# DronePCB_2.net
KiCad netlist of a schematic drawn in Altium Designer
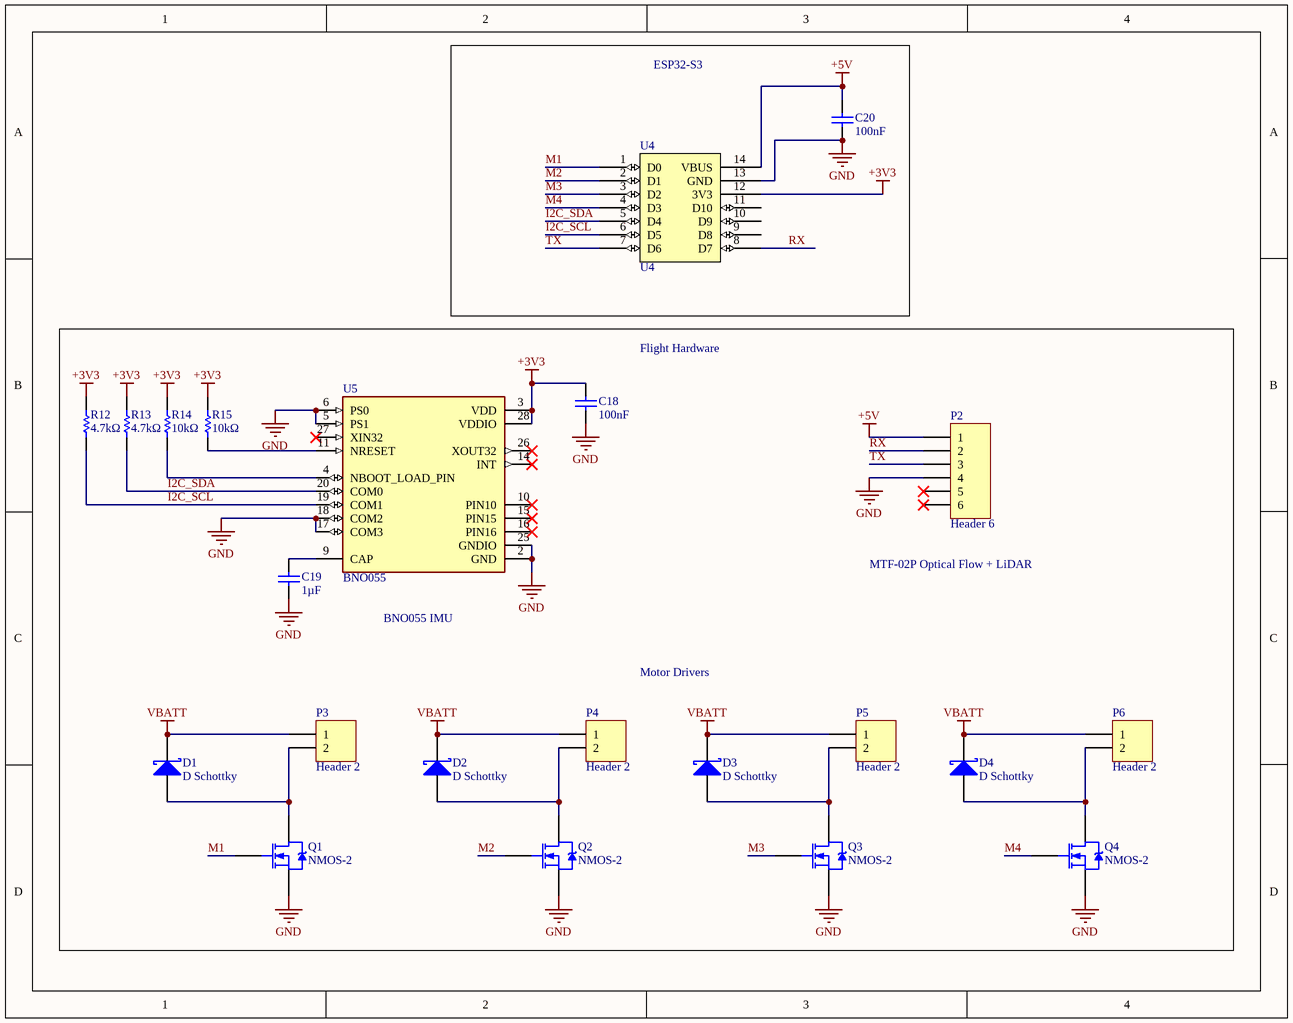
[diagram p0: DronePCB_2.SchDoc]

(export (version "E")
  (design (tool "Eeschema 10.0.6"))
  (components
    (comp (ref "C18")
      (value "100nF")
      (footprint "RAD-0.3")
      (description "Capacitor")
      (fields (field (name "Comment") "Cap") (field (name "PUBLISHER") "Altium Limited"))
      (libsource (lib "Miscellaneous Devices") (part "Cap"))
    )
    (comp (ref "C19")
      (value "1µF")
      (footprint "RAD-0.3")
      (description "Capacitor")
      (fields (field (name "Comment") "Cap") (field (name "PUBLISHER") "Altium Limited"))
      (libsource (lib "Miscellaneous Devices") (part "Cap"))
    )
    (comp (ref "C20")
      (value "100nF")
      (footprint "RAD-0.3")
      (description "Capacitor")
      (fields (field (name "Comment") "Cap") (field (name "PUBLISHER") "Altium Limited"))
      (libsource (lib "Miscellaneous Devices") (part "Cap"))
    )
    (comp (ref "D1")
      (value "D Schottky")
      (footprint "SMB")
      (description "Schottky Diode")
      (fields (field (name "PUBLISHER") "Altium Limited"))
      (libsource (lib "Miscellaneous Devices") (part "D Schottky"))
    )
    (comp (ref "D2")
      (value "D Schottky")
      (footprint "SMB")
      (description "Schottky Diode")
      (fields (field (name "PUBLISHER") "Altium Limited"))
      (libsource (lib "Miscellaneous Devices") (part "D Schottky"))
    )
    (comp (ref "D3")
      (value "D Schottky")
      (footprint "SMB")
      (description "Schottky Diode")
      (fields (field (name "PUBLISHER") "Altium Limited"))
      (libsource (lib "Miscellaneous Devices") (part "D Schottky"))
    )
    (comp (ref "D4")
      (value "D Schottky")
      (footprint "SMB")
      (description "Schottky Diode")
      (fields (field (name "PUBLISHER") "Altium Limited"))
      (libsource (lib "Miscellaneous Devices") (part "D Schottky"))
    )
    (comp (ref "P2")
      (value "Header 6")
      (footprint "HDR1X6")
      (description "Header, 6-Pin")
      (fields (field (name "PUBLISHER") "Altium Limited"))
      (libsource (lib "Miscellaneous Connectors") (part "Header 6"))
    )
    (comp (ref "P3")
      (value "Header 2")
      (footprint "HDR1X2")
      (description "Header, 2-Pin")
      (fields (field (name "PUBLISHER") "Altium Limited"))
      (libsource (lib "Miscellaneous Connectors") (part "Header 2"))
    )
    (comp (ref "P4")
      (value "Header 2")
      (footprint "HDR1X2")
      (description "Header, 2-Pin")
      (fields (field (name "PUBLISHER") "Altium Limited"))
      (libsource (lib "Miscellaneous Connectors") (part "Header 2"))
    )
    (comp (ref "P5")
      (value "Header 2")
      (footprint "HDR1X2")
      (description "Header, 2-Pin")
      (fields (field (name "PUBLISHER") "Altium Limited"))
      (libsource (lib "Miscellaneous Connectors") (part "Header 2"))
    )
    (comp (ref "P6")
      (value "Header 2")
      (footprint "HDR1X2")
      (description "Header, 2-Pin")
      (fields (field (name "PUBLISHER") "Altium Limited"))
      (libsource (lib "Miscellaneous Connectors") (part "Header 2"))
    )
    (comp (ref "Q1")
      (value "NMOS-2")
      (footprint "TO-220AB")
      (description "N-Channel Power MOSFET")
      (fields (field (name "PUBLISHER") "Altium Limited"))
      (libsource (lib "Miscellaneous Devices") (part "NMOS-2"))
    )
    (comp (ref "Q2")
      (value "NMOS-2")
      (footprint "TO-220AB")
      (description "N-Channel Power MOSFET")
      (fields (field (name "PUBLISHER") "Altium Limited"))
      (libsource (lib "Miscellaneous Devices") (part "NMOS-2"))
    )
    (comp (ref "Q3")
      (value "NMOS-2")
      (footprint "TO-220AB")
      (description "N-Channel Power MOSFET")
      (fields (field (name "PUBLISHER") "Altium Limited"))
      (libsource (lib "Miscellaneous Devices") (part "NMOS-2"))
    )
    (comp (ref "Q4")
      (value "NMOS-2")
      (footprint "TO-220AB")
      (description "N-Channel Power MOSFET")
      (fields (field (name "PUBLISHER") "Altium Limited"))
      (libsource (lib "Miscellaneous Devices") (part "NMOS-2"))
    )
    (comp (ref "R12")
      (value "4.7kΩ")
      (footprint "AXIAL-0.3")
      (description "Resistor")
      (fields (field (name "Comment") "Res1") (field (name "PUBLISHER") "Altium Limited"))
      (libsource (lib "Miscellaneous Devices") (part "Res1"))
    )
    (comp (ref "R13")
      (value "4.7kΩ")
      (footprint "AXIAL-0.3")
      (description "Resistor")
      (fields (field (name "Comment") "Res1") (field (name "PUBLISHER") "Altium Limited"))
      (libsource (lib "Miscellaneous Devices") (part "Res1"))
    )
    (comp (ref "R14")
      (value "10kΩ")
      (footprint "AXIAL-0.3")
      (description "Resistor")
      (fields (field (name "Comment") "Res1") (field (name "PUBLISHER") "Altium Limited"))
      (libsource (lib "Miscellaneous Devices") (part "Res1"))
    )
    (comp (ref "R15")
      (value "10kΩ")
      (footprint "AXIAL-0.3")
      (description "Resistor")
      (fields (field (name "Comment") "Res1") (field (name "PUBLISHER") "Altium Limited"))
      (libsource (lib "Miscellaneous Devices") (part "Res1"))
    )
    (comp (ref "U4") (value "U4") (libsource (lib "DronePCB_Main") (part "ESP32S3")))
    (comp (ref "U5")
      (value "BNO055")
      (footprint "LGA28R50P4X10_380X520X100:LGA28R50P4X10_380X520X100")
      (description "BNO055 9-axis Absolute Orientation Sensor ( SiP ) w/Sensors and Sensor Fusion")
      (libsource (lib "DronePCB_Main") (part "BNO055"))
    )
  )
  (nets
    (net (code "1") (name "+3V3") (class "Default")
      (node (ref "C18") (pin "2") (pinfunction "2_2") (pintype "passive"))
      (node (ref "R12") (pin "2") (pinfunction "2_2") (pintype "passive"))
      (node (ref "R13") (pin "2") (pinfunction "2_2") (pintype "passive"))
      (node (ref "R14") (pin "1") (pinfunction "1_1") (pintype "passive"))
      (node (ref "R15") (pin "1") (pinfunction "1_1") (pintype "passive"))
      (node (ref "U4") (pin "12") (pinfunction "3V3_12") (pintype "power_in"))
      (node (ref "U5") (pin "28") (pinfunction "VDDIO_28") (pintype "power_in"))
      (node (ref "U5") (pin "3") (pinfunction "VDD_3") (pintype "power_in"))
    )
    (net (code "2") (name "+5V") (class "Default")
      (node (ref "C20") (pin "2") (pinfunction "2_2") (pintype "passive"))
      (node (ref "P2") (pin "1") (pinfunction "1_1") (pintype "passive"))
      (node (ref "U4") (pin "14") (pinfunction "VBUS_14") (pintype "power_in"))
    )
    (net (code "3") (name "/I2C_SCL") (class "Default")
      (node (ref "R12") (pin "1") (pinfunction "1_1") (pintype "passive"))
      (node (ref "U4") (pin "6") (pinfunction "D5_6") (pintype "bidirectional"))
      (node (ref "U5") (pin "19") (pinfunction "COM1_19") (pintype "bidirectional"))
    )
    (net (code "4") (name "/I2C_SDA") (class "Default")
      (node (ref "R13") (pin "1") (pinfunction "1_1") (pintype "passive"))
      (node (ref "U4") (pin "5") (pinfunction "D4_5") (pintype "bidirectional"))
      (node (ref "U5") (pin "20") (pinfunction "COM0_20") (pintype "bidirectional"))
    )
    (net (code "5") (name "/M1") (class "Default")
      (node (ref "Q1") (pin "1") (pinfunction "G_1") (pintype "passive"))
      (node (ref "U4") (pin "1") (pinfunction "D0_1") (pintype "bidirectional"))
    )
    (net (code "6") (name "/M2") (class "Default")
      (node (ref "Q2") (pin "1") (pinfunction "G_1") (pintype "passive"))
      (node (ref "U4") (pin "2") (pinfunction "D1_2") (pintype "bidirectional"))
    )
    (net (code "7") (name "/M3") (class "Default")
      (node (ref "Q3") (pin "1") (pinfunction "G_1") (pintype "passive"))
      (node (ref "U4") (pin "3") (pinfunction "D2_3") (pintype "bidirectional"))
    )
    (net (code "8") (name "/M4") (class "Default")
      (node (ref "Q4") (pin "1") (pinfunction "G_1") (pintype "passive"))
      (node (ref "U4") (pin "4") (pinfunction "D3_4") (pintype "bidirectional"))
    )
    (net (code "9") (name "/RX") (class "Default")
      (node (ref "P2") (pin "2") (pinfunction "2_2") (pintype "passive"))
      (node (ref "U4") (pin "8") (pinfunction "D7_8") (pintype "bidirectional"))
    )
    (net (code "10") (name "/TX") (class "Default")
      (node (ref "P2") (pin "3") (pinfunction "3_3") (pintype "passive"))
      (node (ref "U4") (pin "7") (pinfunction "D6_7") (pintype "bidirectional"))
    )
    (net (code "11") (name "GND") (class "Default")
      (node (ref "C18") (pin "1") (pinfunction "1_1") (pintype "passive"))
      (node (ref "C19") (pin "1") (pinfunction "1_1") (pintype "passive"))
      (node (ref "C20") (pin "1") (pinfunction "1_1") (pintype "passive"))
      (node (ref "P2") (pin "4") (pinfunction "4_4") (pintype "passive"))
      (node (ref "Q1") (pin "3") (pinfunction "S_3") (pintype "passive"))
      (node (ref "Q2") (pin "3") (pinfunction "S_3") (pintype "passive"))
      (node (ref "Q3") (pin "3") (pinfunction "S_3") (pintype "passive"))
      (node (ref "Q4") (pin "3") (pinfunction "S_3") (pintype "passive"))
      (node (ref "U4") (pin "13") (pinfunction "GND_13") (pintype "power_in"))
      (node (ref "U5") (pin "17") (pinfunction "COM3_17") (pintype "bidirectional"))
      (node (ref "U5") (pin "18") (pinfunction "COM2_18") (pintype "bidirectional"))
      (node (ref "U5") (pin "2") (pinfunction "GND_2") (pintype "power_in"))
      (node (ref "U5") (pin "25") (pinfunction "GNDIO_25") (pintype "power_in"))
      (node (ref "U5") (pin "5") (pinfunction "PS1_5") (pintype "input"))
      (node (ref "U5") (pin "6") (pinfunction "PS0_6") (pintype "input"))
    )
    (net (code "12") (name "Net-(D1-A)") (class "Default")
      (node (ref "D1") (pin "1") (pinfunction "A_1") (pintype "passive"))
      (node (ref "P3") (pin "2") (pinfunction "2_2") (pintype "passive"))
      (node (ref "Q1") (pin "2") (pinfunction "D_2") (pintype "passive"))
    )
    (net (code "13") (name "Net-(D2-A)") (class "Default")
      (node (ref "D2") (pin "1") (pinfunction "A_1") (pintype "passive"))
      (node (ref "P4") (pin "2") (pinfunction "2_2") (pintype "passive"))
      (node (ref "Q2") (pin "2") (pinfunction "D_2") (pintype "passive"))
    )
    (net (code "14") (name "Net-(D3-A)") (class "Default")
      (node (ref "D3") (pin "1") (pinfunction "A_1") (pintype "passive"))
      (node (ref "P5") (pin "2") (pinfunction "2_2") (pintype "passive"))
      (node (ref "Q3") (pin "2") (pinfunction "D_2") (pintype "passive"))
    )
    (net (code "15") (name "Net-(D4-A)") (class "Default")
      (node (ref "D4") (pin "1") (pinfunction "A_1") (pintype "passive"))
      (node (ref "P6") (pin "2") (pinfunction "2_2") (pintype "passive"))
      (node (ref "Q4") (pin "2") (pinfunction "D_2") (pintype "passive"))
    )
    (net (code "16") (name "Net-(U5-CAP)") (class "Default")
      (node (ref "C19") (pin "2") (pinfunction "2_2") (pintype "passive"))
      (node (ref "U5") (pin "9") (pinfunction "CAP_9") (pintype "passive"))
    )
    (net (code "17") (name "Net-(U5-NBOOT_LOAD_PIN)") (class "Default")
      (node (ref "R14") (pin "2") (pinfunction "2_2") (pintype "passive"))
      (node (ref "U5") (pin "4") (pinfunction "NBOOT_LOAD_PIN_4") (pintype "bidirectional"))
    )
    (net (code "18") (name "Net-(U5-NRESET)") (class "Default")
      (node (ref "R15") (pin "2") (pinfunction "2_2") (pintype "passive"))
      (node (ref "U5") (pin "11") (pinfunction "NRESET_11") (pintype "input"))
    )
    (net (code "19") (name "VBATT") (class "Default")
      (node (ref "D1") (pin "2") (pinfunction "K_2") (pintype "passive"))
      (node (ref "D2") (pin "2") (pinfunction "K_2") (pintype "passive"))
      (node (ref "D3") (pin "2") (pinfunction "K_2") (pintype "passive"))
      (node (ref "D4") (pin "2") (pinfunction "K_2") (pintype "passive"))
      (node (ref "P3") (pin "1") (pinfunction "1_1") (pintype "passive"))
      (node (ref "P4") (pin "1") (pinfunction "1_1") (pintype "passive"))
      (node (ref "P5") (pin "1") (pinfunction "1_1") (pintype "passive"))
      (node (ref "P6") (pin "1") (pinfunction "1_1") (pintype "passive"))
    )
    (net (code "20") (name "unconnected-(P2-Pad5)") (class "Default")
      (node (ref "P2") (pin "5") (pinfunction "5_5") (pintype "passive+no_connect"))
    )
    (net (code "21") (name "unconnected-(P2-Pad6)") (class "Default")
      (node (ref "P2") (pin "6") (pinfunction "6_6") (pintype "passive+no_connect"))
    )
    (net (code "22") (name "unconnected-(U4-D8-Pad9)") (class "Default")
      (node (ref "U4") (pin "9") (pinfunction "D8_9") (pintype "bidirectional"))
    )
    (net (code "23") (name "unconnected-(U4-D9-Pad10)") (class "Default")
      (node (ref "U4") (pin "10") (pinfunction "D9_10") (pintype "bidirectional"))
    )
    (net (code "24") (name "unconnected-(U4-D10-Pad11)") (class "Default")
      (node (ref "U4") (pin "11") (pinfunction "D10_11") (pintype "bidirectional"))
    )
    (net (code "25") (name "unconnected-(U5-INT-Pad14)") (class "Default")
      (node (ref "U5") (pin "14") (pinfunction "INT_14") (pintype "output+no_connect"))
    )
    (net (code "26") (name "unconnected-(U5-PIN10-Pad10)") (class "Default")
      (node (ref "U5") (pin "10") (pinfunction "PIN10_10") (pintype "power_in+no_connect"))
    )
    (net (code "27") (name "unconnected-(U5-PIN15-Pad15)") (class "Default")
      (node (ref "U5") (pin "15") (pinfunction "PIN15_15") (pintype "power_in+no_connect"))
    )
    (net (code "28") (name "unconnected-(U5-PIN16-Pad16)") (class "Default")
      (node (ref "U5") (pin "16") (pinfunction "PIN16_16") (pintype "power_in+no_connect"))
    )
    (net (code "29") (name "unconnected-(U5-XIN32-Pad27)") (class "Default")
      (node (ref "U5") (pin "27") (pinfunction "XIN32_27") (pintype "input+no_connect"))
    )
    (net (code "30") (name "unconnected-(U5-XOUT32-Pad26)") (class "Default")
      (node (ref "U5") (pin "26") (pinfunction "XOUT32_26") (pintype "output+no_connect"))
    )
  )
)
